# SOC_PinOut.net
KiCad netlist of a schematic drawn in Altium Designer
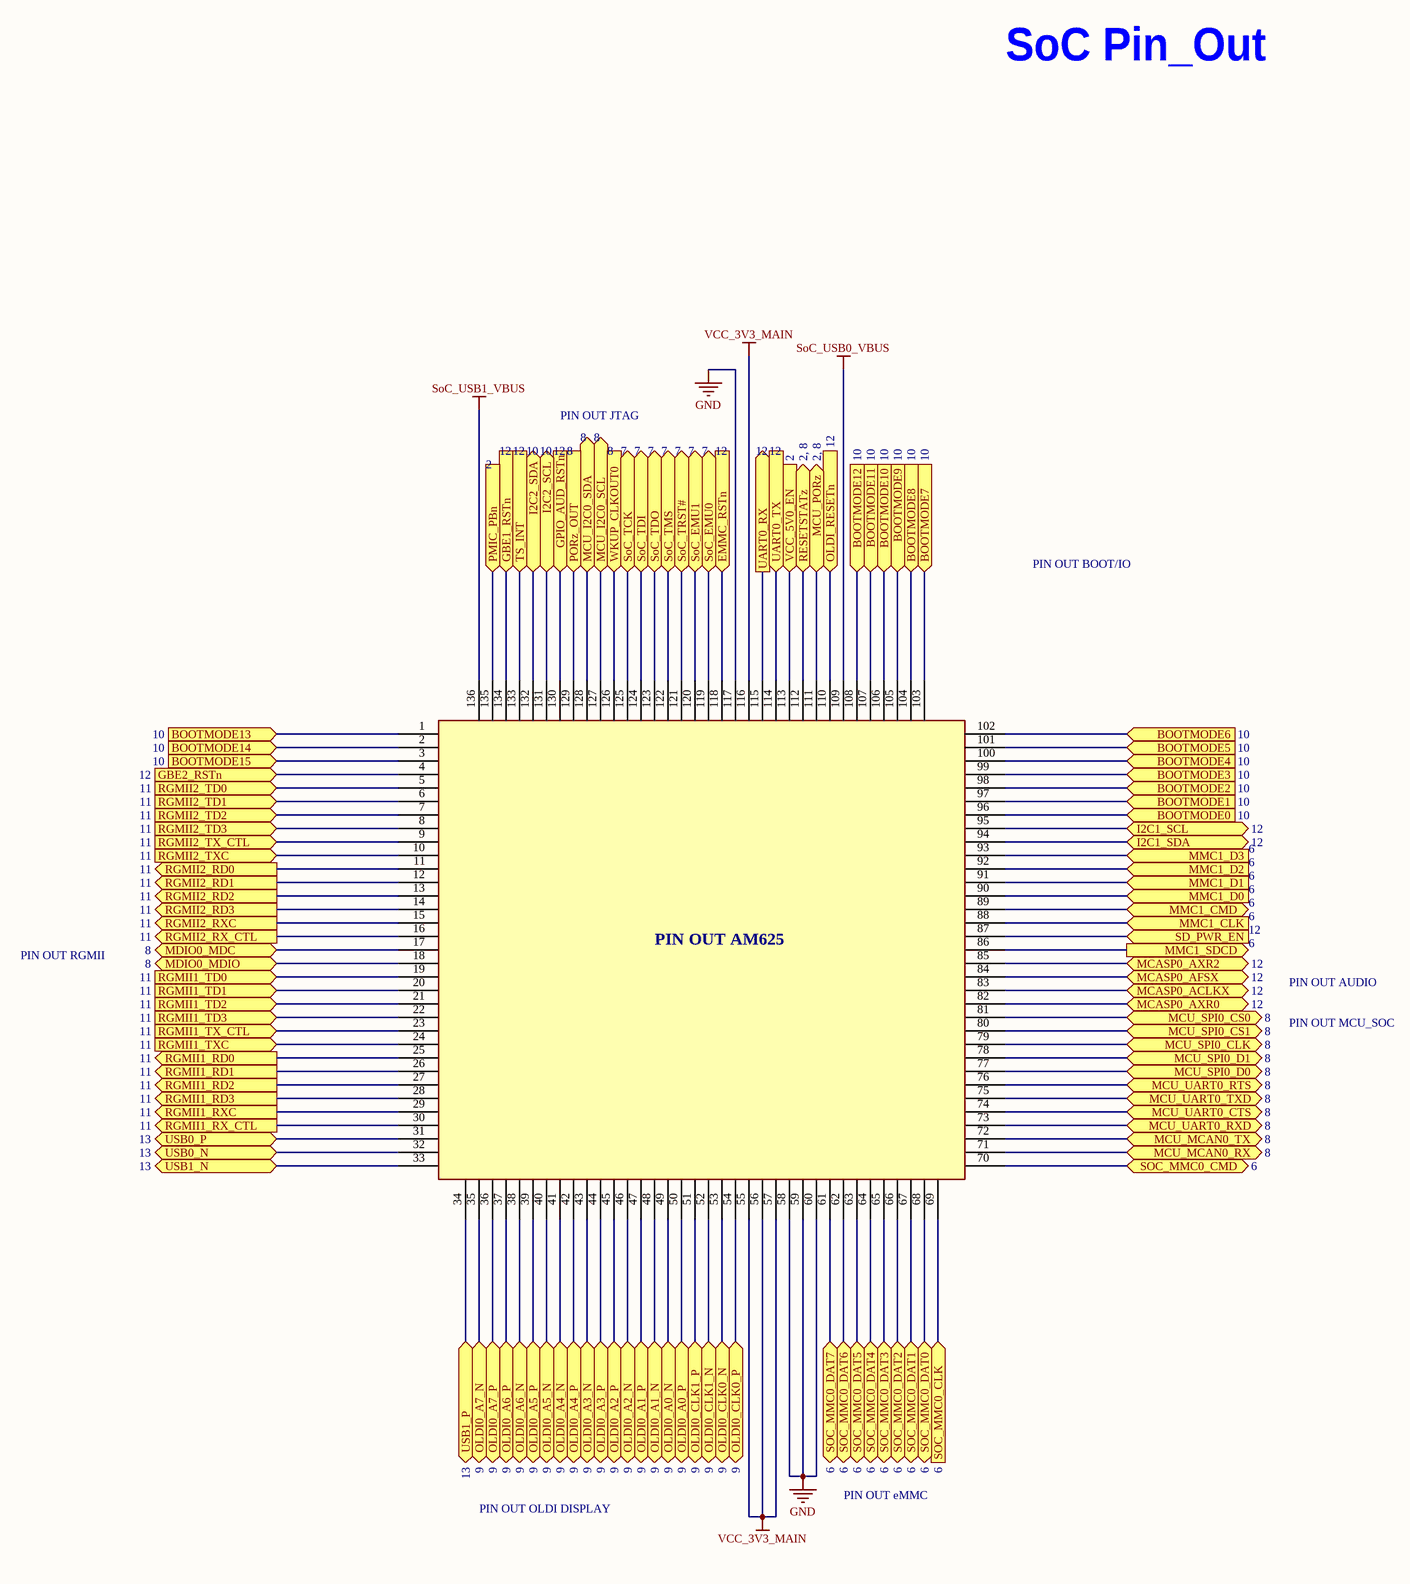
[diagram p0: SOC PinOut.SchDoc]

(export (version "E")
  (design (tool "Eeschema 10.0.6"))
  (components
    (comp (ref "PIN1")
      (value "Pin OUT AM625")
      (footprint "PIN_OUT AM625 - 136PIN")
      (libsource (lib "Schlib AM625") (part "PIN_OUT"))
    )
  )
  (nets
    (net (code "1") (name "/BOOTMODE0") (class "Default")
      (node (ref "PIN1") (pin "96") (pinfunction "96_96") (pintype "passive"))
    )
    (net (code "2") (name "/BOOTMODE1") (class "Default")
      (node (ref "PIN1") (pin "97") (pinfunction "97_97") (pintype "passive"))
    )
    (net (code "3") (name "/BOOTMODE2") (class "Default")
      (node (ref "PIN1") (pin "98") (pinfunction "98_98") (pintype "passive"))
    )
    (net (code "4") (name "/BOOTMODE3") (class "Default")
      (node (ref "PIN1") (pin "99") (pinfunction "99_99") (pintype "passive"))
    )
    (net (code "5") (name "/BOOTMODE4") (class "Default")
      (node (ref "PIN1") (pin "100") (pinfunction "100_100") (pintype "passive"))
    )
    (net (code "6") (name "/BOOTMODE5") (class "Default")
      (node (ref "PIN1") (pin "101") (pinfunction "101_101") (pintype "passive"))
    )
    (net (code "7") (name "/BOOTMODE6") (class "Default")
      (node (ref "PIN1") (pin "102") (pinfunction "102_102") (pintype "passive"))
    )
    (net (code "8") (name "/BOOTMODE7") (class "Default")
      (node (ref "PIN1") (pin "103") (pinfunction "103_103") (pintype "passive"))
    )
    (net (code "9") (name "/BOOTMODE8") (class "Default")
      (node (ref "PIN1") (pin "104") (pinfunction "104_104") (pintype "passive"))
    )
    (net (code "10") (name "/BOOTMODE9") (class "Default")
      (node (ref "PIN1") (pin "105") (pinfunction "105_105") (pintype "passive"))
    )
    (net (code "11") (name "/BOOTMODE10") (class "Default")
      (node (ref "PIN1") (pin "106") (pinfunction "106_106") (pintype "passive"))
    )
    (net (code "12") (name "/BOOTMODE11") (class "Default")
      (node (ref "PIN1") (pin "107") (pinfunction "107_107") (pintype "passive"))
    )
    (net (code "13") (name "/BOOTMODE12") (class "Default")
      (node (ref "PIN1") (pin "108") (pinfunction "108_108") (pintype "passive"))
    )
    (net (code "14") (name "/BOOTMODE13") (class "Default")
      (node (ref "PIN1") (pin "1") (pinfunction "1_1") (pintype "passive"))
    )
    (net (code "15") (name "/BOOTMODE14") (class "Default")
      (node (ref "PIN1") (pin "2") (pinfunction "2_2") (pintype "passive"))
    )
    (net (code "16") (name "/BOOTMODE15") (class "Default")
      (node (ref "PIN1") (pin "3") (pinfunction "3_3") (pintype "passive"))
    )
    (net (code "17") (name "/EMMC_RSTn") (class "Default")
      (node (ref "PIN1") (pin "118") (pinfunction "118_118") (pintype "passive"))
    )
    (net (code "18") (name "/GBE1_RSTn") (class "Default")
      (node (ref "PIN1") (pin "134") (pinfunction "134_134") (pintype "passive"))
    )
    (net (code "19") (name "/GBE2_RSTn") (class "Default")
      (node (ref "PIN1") (pin "4") (pinfunction "4_4") (pintype "passive"))
    )
    (net (code "20") (name "/GPIO_AUD_RSTn") (class "Default")
      (node (ref "PIN1") (pin "130") (pinfunction "130_130") (pintype "passive"))
    )
    (net (code "21") (name "/I2C1_SCL") (class "Default")
      (node (ref "PIN1") (pin "95") (pinfunction "95_95") (pintype "passive"))
    )
    (net (code "22") (name "/I2C1_SDA") (class "Default")
      (node (ref "PIN1") (pin "94") (pinfunction "94_94") (pintype "passive"))
    )
    (net (code "23") (name "/I2C2_SCL") (class "Default")
      (node (ref "PIN1") (pin "131") (pinfunction "131_131") (pintype "passive"))
    )
    (net (code "24") (name "/I2C2_SDA") (class "Default")
      (node (ref "PIN1") (pin "132") (pinfunction "132_132") (pintype "passive"))
    )
    (net (code "25") (name "/MCASP0_ACLKX") (class "Default")
      (node (ref "PIN1") (pin "83") (pinfunction "83_83") (pintype "passive"))
    )
    (net (code "26") (name "/MCASP0_AFSX") (class "Default")
      (node (ref "PIN1") (pin "84") (pinfunction "84_84") (pintype "passive"))
    )
    (net (code "27") (name "/MCASP0_AXR0") (class "Default")
      (node (ref "PIN1") (pin "82") (pinfunction "82_82") (pintype "passive"))
    )
    (net (code "28") (name "/MCASP0_AXR2") (class "Default")
      (node (ref "PIN1") (pin "85") (pinfunction "85_85") (pintype "passive"))
    )
    (net (code "29") (name "/MCU_I2C0_SCL") (class "Default")
      (node (ref "PIN1") (pin "127") (pinfunction "127_127") (pintype "passive"))
    )
    (net (code "30") (name "/MCU_I2C0_SDA") (class "Default")
      (node (ref "PIN1") (pin "128") (pinfunction "128_128") (pintype "passive"))
    )
    (net (code "31") (name "/MCU_MCAN0_RX") (class "Default")
      (node (ref "PIN1") (pin "71") (pinfunction "71_71") (pintype "passive"))
    )
    (net (code "32") (name "/MCU_MCAN0_TX") (class "Default")
      (node (ref "PIN1") (pin "72") (pinfunction "72_72") (pintype "passive"))
    )
    (net (code "33") (name "/MCU_PORz") (class "Default")
      (node (ref "PIN1") (pin "111") (pinfunction "111_111") (pintype "passive"))
    )
    (net (code "34") (name "/MCU_SPI0_CLK") (class "Default")
      (node (ref "PIN1") (pin "79") (pinfunction "79_79") (pintype "passive"))
    )
    (net (code "35") (name "/MCU_SPI0_CS0") (class "Default")
      (node (ref "PIN1") (pin "81") (pinfunction "81_81") (pintype "passive"))
    )
    (net (code "36") (name "/MCU_SPI0_CS1") (class "Default")
      (node (ref "PIN1") (pin "80") (pinfunction "80_80") (pintype "passive"))
    )
    (net (code "37") (name "/MCU_SPI0_D0") (class "Default")
      (node (ref "PIN1") (pin "77") (pinfunction "77_77") (pintype "passive"))
    )
    (net (code "38") (name "/MCU_SPI0_D1") (class "Default")
      (node (ref "PIN1") (pin "78") (pinfunction "78_78") (pintype "passive"))
    )
    (net (code "39") (name "/MCU_UART0_CTS") (class "Default")
      (node (ref "PIN1") (pin "74") (pinfunction "74_74") (pintype "passive"))
    )
    (net (code "40") (name "/MCU_UART0_RTS") (class "Default")
      (node (ref "PIN1") (pin "76") (pinfunction "76_76") (pintype "passive"))
    )
    (net (code "41") (name "/MCU_UART0_RXD") (class "Default")
      (node (ref "PIN1") (pin "73") (pinfunction "73_73") (pintype "passive"))
    )
    (net (code "42") (name "/MCU_UART0_TXD") (class "Default")
      (node (ref "PIN1") (pin "75") (pinfunction "75_75") (pintype "passive"))
    )
    (net (code "43") (name "/MDIO0_MDC") (class "Default")
      (node (ref "PIN1") (pin "17") (pinfunction "17_17") (pintype "passive"))
    )
    (net (code "44") (name "/MDIO0_MDIO") (class "Default")
      (node (ref "PIN1") (pin "18") (pinfunction "18_18") (pintype "passive"))
    )
    (net (code "45") (name "/MMC1_CLK") (class "Default")
      (node (ref "PIN1") (pin "88") (pinfunction "88_88") (pintype "passive"))
    )
    (net (code "46") (name "/MMC1_CMD") (class "Default")
      (node (ref "PIN1") (pin "89") (pinfunction "89_89") (pintype "passive"))
    )
    (net (code "47") (name "/MMC1_D0") (class "Default")
      (node (ref "PIN1") (pin "90") (pinfunction "90_90") (pintype "passive"))
    )
    (net (code "48") (name "/MMC1_D1") (class "Default")
      (node (ref "PIN1") (pin "91") (pinfunction "91_91") (pintype "passive"))
    )
    (net (code "49") (name "/MMC1_D2") (class "Default")
      (node (ref "PIN1") (pin "92") (pinfunction "92_92") (pintype "passive"))
    )
    (net (code "50") (name "/MMC1_D3") (class "Default")
      (node (ref "PIN1") (pin "93") (pinfunction "93_93") (pintype "passive"))
    )
    (net (code "51") (name "/MMC1_SDCD") (class "Default")
      (node (ref "PIN1") (pin "86") (pinfunction "86_86") (pintype "passive"))
    )
    (net (code "52") (name "/OLDI0_A0_N") (class "Default")
      (node (ref "PIN1") (pin "49") (pinfunction "49_49") (pintype "passive"))
    )
    (net (code "53") (name "/OLDI0_A0_P") (class "Default")
      (node (ref "PIN1") (pin "50") (pinfunction "50_50") (pintype "passive"))
    )
    (net (code "54") (name "/OLDI0_A1_N") (class "Default")
      (node (ref "PIN1") (pin "48") (pinfunction "48_48") (pintype "passive"))
    )
    (net (code "55") (name "/OLDI0_A1_P") (class "Default")
      (node (ref "PIN1") (pin "47") (pinfunction "47_47") (pintype "passive"))
    )
    (net (code "56") (name "/OLDI0_A2_N") (class "Default")
      (node (ref "PIN1") (pin "46") (pinfunction "46_46") (pintype "passive"))
    )
    (net (code "57") (name "/OLDI0_A2_P") (class "Default")
      (node (ref "PIN1") (pin "45") (pinfunction "45_45") (pintype "passive"))
    )
    (net (code "58") (name "/OLDI0_A3_N") (class "Default")
      (node (ref "PIN1") (pin "43") (pinfunction "43_43") (pintype "passive"))
    )
    (net (code "59") (name "/OLDI0_A3_P") (class "Default")
      (node (ref "PIN1") (pin "44") (pinfunction "44_44") (pintype "passive"))
    )
    (net (code "60") (name "/OLDI0_A4_N") (class "Default")
      (node (ref "PIN1") (pin "41") (pinfunction "41_41") (pintype "passive"))
    )
    (net (code "61") (name "/OLDI0_A4_P") (class "Default")
      (node (ref "PIN1") (pin "42") (pinfunction "42_42") (pintype "passive"))
    )
    (net (code "62") (name "/OLDI0_A5_N") (class "Default")
      (node (ref "PIN1") (pin "40") (pinfunction "40_40") (pintype "passive"))
    )
    (net (code "63") (name "/OLDI0_A5_P") (class "Default")
      (node (ref "PIN1") (pin "39") (pinfunction "39_39") (pintype "passive"))
    )
    (net (code "64") (name "/OLDI0_A6_N") (class "Default")
      (node (ref "PIN1") (pin "38") (pinfunction "38_38") (pintype "passive"))
    )
    (net (code "65") (name "/OLDI0_A6_P") (class "Default")
      (node (ref "PIN1") (pin "37") (pinfunction "37_37") (pintype "passive"))
    )
    (net (code "66") (name "/OLDI0_A7_N") (class "Default")
      (node (ref "PIN1") (pin "35") (pinfunction "35_35") (pintype "passive"))
    )
    (net (code "67") (name "/OLDI0_A7_P") (class "Default")
      (node (ref "PIN1") (pin "36") (pinfunction "36_36") (pintype "passive"))
    )
    (net (code "68") (name "/OLDI0_CLK0_N") (class "Default")
      (node (ref "PIN1") (pin "53") (pinfunction "53_53") (pintype "passive"))
    )
    (net (code "69") (name "/OLDI0_CLK0_P") (class "Default")
      (node (ref "PIN1") (pin "54") (pinfunction "54_54") (pintype "passive"))
    )
    (net (code "70") (name "/OLDI0_CLK1_N") (class "Default")
      (node (ref "PIN1") (pin "52") (pinfunction "52_52") (pintype "passive"))
    )
    (net (code "71") (name "/OLDI0_CLK1_P") (class "Default")
      (node (ref "PIN1") (pin "51") (pinfunction "51_51") (pintype "passive"))
    )
    (net (code "72") (name "/OLDI_RESETn") (class "Default")
      (node (ref "PIN1") (pin "110") (pinfunction "110_110") (pintype "passive"))
    )
    (net (code "73") (name "/PMIC_PBn") (class "Default")
      (node (ref "PIN1") (pin "135") (pinfunction "135_135") (pintype "passive"))
    )
    (net (code "74") (name "/PORz_OUT") (class "Default")
      (node (ref "PIN1") (pin "129") (pinfunction "129_129") (pintype "passive"))
    )
    (net (code "75") (name "/RESETSTATz") (class "Default")
      (node (ref "PIN1") (pin "112") (pinfunction "112_112") (pintype "passive"))
    )
    (net (code "76") (name "/RGMII1_RD0") (class "Default")
      (node (ref "PIN1") (pin "25") (pinfunction "25_25") (pintype "passive"))
    )
    (net (code "77") (name "/RGMII1_RD1") (class "Default")
      (node (ref "PIN1") (pin "26") (pinfunction "26_26") (pintype "passive"))
    )
    (net (code "78") (name "/RGMII1_RD2") (class "Default")
      (node (ref "PIN1") (pin "27") (pinfunction "27_27") (pintype "passive"))
    )
    (net (code "79") (name "/RGMII1_RD3") (class "Default")
      (node (ref "PIN1") (pin "28") (pinfunction "28_28") (pintype "passive"))
    )
    (net (code "80") (name "/RGMII1_RXC") (class "Default")
      (node (ref "PIN1") (pin "29") (pinfunction "29_29") (pintype "passive"))
    )
    (net (code "81") (name "/RGMII1_RX_CTL") (class "Default")
      (node (ref "PIN1") (pin "30") (pinfunction "30_30") (pintype "passive"))
    )
    (net (code "82") (name "/RGMII1_TD0") (class "Default")
      (node (ref "PIN1") (pin "19") (pinfunction "19_19") (pintype "passive"))
    )
    (net (code "83") (name "/RGMII1_TD1") (class "Default")
      (node (ref "PIN1") (pin "20") (pinfunction "20_20") (pintype "passive"))
    )
    (net (code "84") (name "/RGMII1_TD2") (class "Default")
      (node (ref "PIN1") (pin "21") (pinfunction "21_21") (pintype "passive"))
    )
    (net (code "85") (name "/RGMII1_TD3") (class "Default")
      (node (ref "PIN1") (pin "22") (pinfunction "22_22") (pintype "passive"))
    )
    (net (code "86") (name "/RGMII1_TXC") (class "Default")
      (node (ref "PIN1") (pin "24") (pinfunction "24_24") (pintype "passive"))
    )
    (net (code "87") (name "/RGMII1_TX_CTL") (class "Default")
      (node (ref "PIN1") (pin "23") (pinfunction "23_23") (pintype "passive"))
    )
    (net (code "88") (name "/RGMII2_RD0") (class "Default")
      (node (ref "PIN1") (pin "11") (pinfunction "11_11") (pintype "passive"))
    )
    (net (code "89") (name "/RGMII2_RD1") (class "Default")
      (node (ref "PIN1") (pin "12") (pinfunction "12_12") (pintype "passive"))
    )
    (net (code "90") (name "/RGMII2_RD2") (class "Default")
      (node (ref "PIN1") (pin "13") (pinfunction "13_13") (pintype "passive"))
    )
    (net (code "91") (name "/RGMII2_RD3") (class "Default")
      (node (ref "PIN1") (pin "14") (pinfunction "14_14") (pintype "passive"))
    )
    (net (code "92") (name "/RGMII2_RXC") (class "Default")
      (node (ref "PIN1") (pin "15") (pinfunction "15_15") (pintype "passive"))
    )
    (net (code "93") (name "/RGMII2_RX_CTL") (class "Default")
      (node (ref "PIN1") (pin "16") (pinfunction "16_16") (pintype "passive"))
    )
    (net (code "94") (name "/RGMII2_TD0") (class "Default")
      (node (ref "PIN1") (pin "5") (pinfunction "5_5") (pintype "passive"))
    )
    (net (code "95") (name "/RGMII2_TD1") (class "Default")
      (node (ref "PIN1") (pin "6") (pinfunction "6_6") (pintype "passive"))
    )
    (net (code "96") (name "/RGMII2_TD2") (class "Default")
      (node (ref "PIN1") (pin "7") (pinfunction "7_7") (pintype "passive"))
    )
    (net (code "97") (name "/RGMII2_TD3") (class "Default")
      (node (ref "PIN1") (pin "8") (pinfunction "8_8") (pintype "passive"))
    )
    (net (code "98") (name "/RGMII2_TXC") (class "Default")
      (node (ref "PIN1") (pin "10") (pinfunction "10_10") (pintype "passive"))
    )
    (net (code "99") (name "/RGMII2_TX_CTL") (class "Default")
      (node (ref "PIN1") (pin "9") (pinfunction "9_9") (pintype "passive"))
    )
    (net (code "100") (name "/SD_PWR_EN") (class "Default")
      (node (ref "PIN1") (pin "87") (pinfunction "87_87") (pintype "passive"))
    )
    (net (code "101") (name "/SOC_MMC0_CLK") (class "Default")
      (node (ref "PIN1") (pin "69") (pinfunction "69_69") (pintype "passive"))
    )
    (net (code "102") (name "/SOC_MMC0_CMD") (class "Default")
      (node (ref "PIN1") (pin "70") (pinfunction "70_70") (pintype "passive"))
    )
    (net (code "103") (name "/SOC_MMC0_DAT0") (class "Default")
      (node (ref "PIN1") (pin "68") (pinfunction "68_68") (pintype "passive"))
    )
    (net (code "104") (name "/SOC_MMC0_DAT1") (class "Default")
      (node (ref "PIN1") (pin "67") (pinfunction "67_67") (pintype "passive"))
    )
    (net (code "105") (name "/SOC_MMC0_DAT2") (class "Default")
      (node (ref "PIN1") (pin "66") (pinfunction "66_66") (pintype "passive"))
    )
    (net (code "106") (name "/SOC_MMC0_DAT3") (class "Default")
      (node (ref "PIN1") (pin "65") (pinfunction "65_65") (pintype "passive"))
    )
    (net (code "107") (name "/SOC_MMC0_DAT4") (class "Default")
      (node (ref "PIN1") (pin "64") (pinfunction "64_64") (pintype "passive"))
    )
    (net (code "108") (name "/SOC_MMC0_DAT5") (class "Default")
      (node (ref "PIN1") (pin "63") (pinfunction "63_63") (pintype "passive"))
    )
    (net (code "109") (name "/SOC_MMC0_DAT6") (class "Default")
      (node (ref "PIN1") (pin "62") (pinfunction "62_62") (pintype "passive"))
    )
    (net (code "110") (name "/SOC_MMC0_DAT7") (class "Default")
      (node (ref "PIN1") (pin "61") (pinfunction "61_61") (pintype "passive"))
    )
    (net (code "111") (name "/SoC_EMU0") (class "Default")
      (node (ref "PIN1") (pin "119") (pinfunction "119_119") (pintype "passive"))
    )
    (net (code "112") (name "/SoC_EMU1") (class "Default")
      (node (ref "PIN1") (pin "120") (pinfunction "120_120") (pintype "passive"))
    )
    (net (code "113") (name "/SoC_TCK") (class "Default")
      (node (ref "PIN1") (pin "125") (pinfunction "125_125") (pintype "passive"))
    )
    (net (code "114") (name "/SoC_TDI") (class "Default")
      (node (ref "PIN1") (pin "124") (pinfunction "124_124") (pintype "passive"))
    )
    (net (code "115") (name "/SoC_TDO") (class "Default")
      (node (ref "PIN1") (pin "123") (pinfunction "123_123") (pintype "passive"))
    )
    (net (code "116") (name "/SoC_TMS") (class "Default")
      (node (ref "PIN1") (pin "122") (pinfunction "122_122") (pintype "passive"))
    )
    (net (code "117") (name "/SoC_TRST#") (class "Default")
      (node (ref "PIN1") (pin "121") (pinfunction "121_121") (pintype "passive"))
    )
    (net (code "118") (name "/TS_INT") (class "Default")
      (node (ref "PIN1") (pin "133") (pinfunction "133_133") (pintype "passive"))
    )
    (net (code "119") (name "/UART0_RX") (class "Default")
      (node (ref "PIN1") (pin "115") (pinfunction "115_115") (pintype "passive"))
    )
    (net (code "120") (name "/UART0_TX") (class "Default")
      (node (ref "PIN1") (pin "114") (pinfunction "114_114") (pintype "passive"))
    )
    (net (code "121") (name "/USB0_N") (class "Default")
      (node (ref "PIN1") (pin "32") (pinfunction "32_32") (pintype "passive"))
    )
    (net (code "122") (name "/USB0_P") (class "Default")
      (node (ref "PIN1") (pin "31") (pinfunction "31_31") (pintype "passive"))
    )
    (net (code "123") (name "/USB1_N") (class "Default")
      (node (ref "PIN1") (pin "33") (pinfunction "33_33") (pintype "passive"))
    )
    (net (code "124") (name "/USB1_P") (class "Default")
      (node (ref "PIN1") (pin "34") (pinfunction "34_34") (pintype "passive"))
    )
    (net (code "125") (name "/VCC_5V0_EN") (class "Default")
      (node (ref "PIN1") (pin "113") (pinfunction "113_113") (pintype "passive"))
    )
    (net (code "126") (name "/WKUP_CLKOUT0") (class "Default")
      (node (ref "PIN1") (pin "126") (pinfunction "126_126") (pintype "passive"))
    )
    (net (code "127") (name "GND") (class "Default")
      (node (ref "PIN1") (pin "117") (pinfunction "117_117") (pintype "passive"))
      (node (ref "PIN1") (pin "58") (pinfunction "58_58") (pintype "passive"))
      (node (ref "PIN1") (pin "59") (pinfunction "59_59") (pintype "passive"))
      (node (ref "PIN1") (pin "60") (pinfunction "60_60") (pintype "passive"))
    )
    (net (code "128") (name "SoC_USB0_VBUS") (class "Default")
      (node (ref "PIN1") (pin "109") (pinfunction "109_109") (pintype "passive"))
    )
    (net (code "129") (name "SoC_USB1_VBUS") (class "Default")
      (node (ref "PIN1") (pin "136") (pinfunction "136_136") (pintype "passive"))
    )
    (net (code "130") (name "VCC_3V3_MAIN") (class "Default")
      (node (ref "PIN1") (pin "116") (pinfunction "116_116") (pintype "passive"))
      (node (ref "PIN1") (pin "55") (pinfunction "55_55") (pintype "passive"))
      (node (ref "PIN1") (pin "56") (pinfunction "56_56") (pintype "passive"))
      (node (ref "PIN1") (pin "57") (pinfunction "57_57") (pintype "passive"))
    )
  )
)
